# Sheet1.net
KiCad netlist of a schematic drawn in Altium Designer
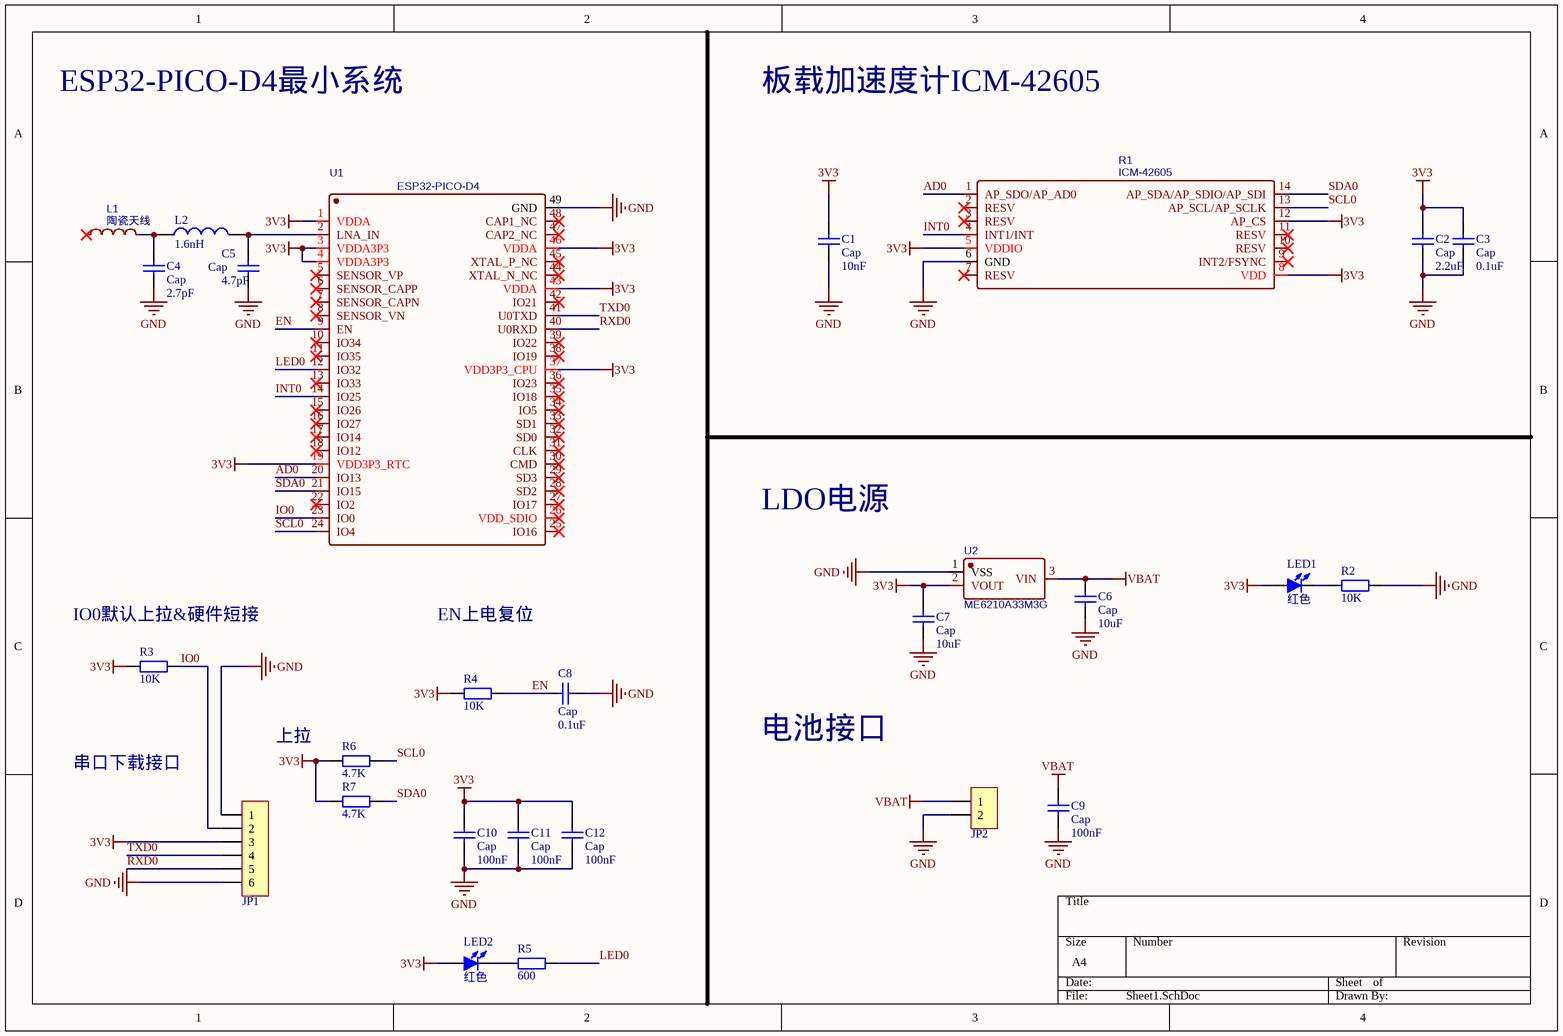
[diagram p0: Sheet1.SchDoc]

(export (version "E")
  (design (tool "Eeschema 10.0.6"))
  (components
    (comp (ref "C1")
      (value "Cap")
      (footprint "C 0402_L")
      (description "Capacitor")
      (fields (field (name "ALTIUM_VALUE") "10nF") (field (name "PUBLISHER") "Altium Limited"))
      (libsource (lib "Miscellaneous Devices") (part "Cap"))
    )
    (comp (ref "C2")
      (value "Cap")
      (footprint "C 0402_L")
      (description "Capacitor")
      (fields (field (name "ALTIUM_VALUE") "2.2uF") (field (name "PUBLISHER") "Altium Limited"))
      (libsource (lib "Miscellaneous Devices") (part "Cap"))
    )
    (comp (ref "C3")
      (value "Cap")
      (footprint "C 0402_L")
      (description "Capacitor")
      (fields (field (name "ALTIUM_VALUE") "0.1uF") (field (name "PUBLISHER") "Altium Limited"))
      (libsource (lib "Miscellaneous Devices") (part "Cap"))
    )
    (comp (ref "C4")
      (value "Cap")
      (footprint "C 0402_L")
      (description "Capacitor")
      (fields (field (name "ALTIUM_VALUE") "2.7pF") (field (name "PUBLISHER") "Altium Limited"))
      (libsource (lib "Miscellaneous Devices") (part "Cap"))
    )
    (comp (ref "C5")
      (value "Cap")
      (footprint "C 0402_L")
      (description "Capacitor")
      (fields (field (name "ALTIUM_VALUE") "4.7pF") (field (name "PUBLISHER") "Altium Limited"))
      (libsource (lib "Miscellaneous Devices") (part "Cap"))
    )
    (comp (ref "C6")
      (value "Cap")
      (footprint "C 0402_L")
      (description "Capacitor")
      (fields (field (name "ALTIUM_VALUE") "10uF") (field (name "PUBLISHER") "Altium Limited"))
      (libsource (lib "Miscellaneous Devices") (part "Cap"))
    )
    (comp (ref "C7")
      (value "Cap")
      (footprint "C 0402_L")
      (description "Capacitor")
      (fields (field (name "ALTIUM_VALUE") "10uF") (field (name "PUBLISHER") "Altium Limited"))
      (libsource (lib "Miscellaneous Devices") (part "Cap"))
    )
    (comp (ref "C8")
      (value "Cap")
      (footprint "C 0402_L")
      (description "Capacitor")
      (fields (field (name "ALTIUM_VALUE") "0.1uF") (field (name "PUBLISHER") "Altium Limited"))
      (libsource (lib "Miscellaneous Devices") (part "Cap"))
    )
    (comp (ref "C9")
      (value "Cap")
      (footprint "C 0402_L")
      (description "Capacitor")
      (fields (field (name "ALTIUM_VALUE") "100nF") (field (name "PUBLISHER") "Altium Limited"))
      (libsource (lib "Miscellaneous Devices") (part "Cap"))
    )
    (comp (ref "C10")
      (value "Cap")
      (footprint "C 0402_L")
      (description "Capacitor")
      (fields (field (name "ALTIUM_VALUE") "100nF") (field (name "PUBLISHER") "Altium Limited"))
      (libsource (lib "Miscellaneous Devices") (part "Cap"))
    )
    (comp (ref "C11")
      (value "Cap")
      (footprint "C 0402_L")
      (description "Capacitor")
      (fields (field (name "ALTIUM_VALUE") "100nF") (field (name "PUBLISHER") "Altium Limited"))
      (libsource (lib "Miscellaneous Devices") (part "Cap"))
    )
    (comp (ref "C12")
      (value "Cap")
      (footprint "C 0402_L")
      (description "Capacitor")
      (fields (field (name "ALTIUM_VALUE") "100nF") (field (name "PUBLISHER") "Altium Limited"))
      (libsource (lib "Miscellaneous Devices") (part "Cap"))
    )
    (comp (ref "JP1")
      (value "HDR-1X6")
      (footprint "debug")
      (description "6P接插件")
      (fields (field (name "版权归属") "源创客"))
      (libsource (lib "Basic_Integrated_Library") (part "Header 6"))
    )
    (comp (ref "JP2")
      (value "HDR-1X2")
      (footprint "电池焊接口")
      (description "2P接插件")
      (fields (field (name "版权归属") "源创客"))
      (libsource (lib "Basic_Integrated_Library") (part "Header 2"))
    )
    (comp (ref "L1")
      (value "陶瓷天线")
      (footprint "Huaxin")
      (fields
        (field (name "BOM_SUPPLIER PART") "C127620")
        (field (name "BOM_MANUFACTURER PART") "RFECA3216060A1T")
        (field (name "CONTRIBUTOR") "LCSC")
      )
      (libsource (lib "altium-import") (part "root_0_Huaxin_"))
    )
    (comp (ref "L2")
      (value "1.6nH")
      (footprint "L 0402")
      (description "小功率贴片电感")
      (fields (field (name "版权归属") "源创客"))
      (libsource (lib "Basic_Integrated_Library") (part "L"))
    )
    (comp (ref "LED1")
      (value "红色")
      (footprint "LED 0805G")
      (description "贴片LED")
      (fields (field (name "版权归属") "源创客"))
      (libsource (lib "Basic_Integrated_Library") (part "LED-SMD"))
    )
    (comp (ref "LED2")
      (value "红色")
      (footprint "LED 0805G")
      (description "贴片LED")
      (fields (field (name "版权归属") "源创客"))
      (libsource (lib "Basic_Integrated_Library") (part "LED-SMD"))
    )
    (comp (ref "R1")
      (value "ICM-42605")
      (footprint "ICM-42605")
      (fields (field (name "BOM_SUPPLIER PART") "C2655099") (field (name "CONTRIBUTOR") "LCSC"))
      (libsource (lib "altium-import") (part "root_0_ICM-42605_"))
    )
    (comp (ref "R2")
      (value "10K")
      (footprint "R 0402_L")
      (description "贴片电阻")
      (fields (field (name "版权归属") "源创客"))
      (libsource (lib "Basic_Integrated_Library") (part "R"))
    )
    (comp (ref "R3")
      (value "10K")
      (footprint "R 0402_L")
      (description "贴片电阻")
      (fields (field (name "版权归属") "源创客"))
      (libsource (lib "Basic_Integrated_Library") (part "R"))
    )
    (comp (ref "R4")
      (value "10K")
      (footprint "R 0402_L")
      (description "贴片电阻")
      (fields (field (name "版权归属") "源创客"))
      (libsource (lib "Basic_Integrated_Library") (part "R"))
    )
    (comp (ref "R5")
      (value "600")
      (footprint "R 0402_L")
      (description "贴片电阻")
      (fields (field (name "版权归属") "源创客"))
      (libsource (lib "Basic_Integrated_Library") (part "R"))
    )
    (comp (ref "R6")
      (value "4.7K")
      (footprint "R 0402_L")
      (description "贴片电阻")
      (fields (field (name "版权归属") "源创客"))
      (libsource (lib "Basic_Integrated_Library") (part "R"))
    )
    (comp (ref "R7")
      (value "4.7K")
      (footprint "R 0402_L")
      (description "贴片电阻")
      (fields (field (name "版权归属") "源创客"))
      (libsource (lib "Basic_Integrated_Library") (part "R"))
    )
    (comp (ref "U1")
      (value "ESP32-PICO-D4")
      (footprint "ESP32-PICO-D4")
      (fields (field (name "BOM_SUPPLIER PART") "C193707") (field (name "CONTRIBUTOR") "LCSC"))
      (libsource (lib "altium-import") (part "root_0_ESP32-PICO-D4_"))
    )
    (comp (ref "U2")
      (value "ME6210A33M3G")
      (footprint "ME6210A33M3G")
      (fields (field (name "BOM_SUPPLIER PART") "C236680") (field (name "CONTRIBUTOR") "LCSC"))
      (libsource (lib "altium-import") (part "root_0_ME6210A33M3G_"))
    )
  )
  (nets
    (net (code "1") (name "/AD0") (class "Default")
      (node (ref "R1") (pin "1") (pinfunction "AP_SDO/AP_AD0_1") (pintype "passive"))
      (node (ref "U1") (pin "20") (pinfunction "IO13_20") (pintype "passive"))
    )
    (net (code "2") (name "/EN") (class "Default")
      (node (ref "C8") (pin "2") (pinfunction "2_2") (pintype "passive"))
      (node (ref "R4") (pin "2") (pinfunction "2_2") (pintype "passive"))
      (node (ref "U1") (pin "9") (pinfunction "EN_9") (pintype "passive"))
    )
    (net (code "3") (name "/INT0") (class "Default")
      (node (ref "R1") (pin "4") (pinfunction "INT1/INT_4") (pintype "passive"))
      (node (ref "U1") (pin "14") (pinfunction "IO25_14") (pintype "passive"))
    )
    (net (code "4") (name "/IO0") (class "Default")
      (node (ref "JP1") (pin "2") (pinfunction "2_2") (pintype "passive"))
      (node (ref "R3") (pin "2") (pinfunction "2_2") (pintype "passive"))
      (node (ref "U1") (pin "23") (pinfunction "IO0_23") (pintype "passive"))
    )
    (net (code "5") (name "/LED0") (class "Default")
      (node (ref "R5") (pin "2") (pinfunction "2_2") (pintype "passive"))
      (node (ref "U1") (pin "12") (pinfunction "IO32_12") (pintype "passive"))
    )
    (net (code "6") (name "/RXD0") (class "Default")
      (node (ref "JP1") (pin "5") (pinfunction "5_5") (pintype "passive"))
      (node (ref "U1") (pin "40") (pinfunction "U0RXD_40") (pintype "passive"))
    )
    (net (code "7") (name "/SCL0") (class "Default")
      (node (ref "R1") (pin "13") (pinfunction "AP_SCL/AP_SCLK_13") (pintype "passive"))
      (node (ref "R6") (pin "2") (pinfunction "2_2") (pintype "passive"))
      (node (ref "U1") (pin "24") (pinfunction "IO4_24") (pintype "passive"))
    )
    (net (code "8") (name "/SDA0") (class "Default")
      (node (ref "R1") (pin "14") (pinfunction "AP_SDA/AP_SDIO/AP_SDI_14") (pintype "passive"))
      (node (ref "R7") (pin "2") (pinfunction "2_2") (pintype "passive"))
      (node (ref "U1") (pin "21") (pinfunction "IO15_21") (pintype "passive"))
    )
    (net (code "9") (name "/TXD0") (class "Default")
      (node (ref "JP1") (pin "4") (pinfunction "4_4") (pintype "passive"))
      (node (ref "U1") (pin "41") (pinfunction "U0TXD_41") (pintype "passive"))
    )
    (net (code "10") (name "3V3") (class "Default")
      (node (ref "C1") (pin "2") (pinfunction "2_2") (pintype "passive"))
      (node (ref "C10") (pin "1") (pinfunction "1_1") (pintype "passive"))
      (node (ref "C11") (pin "1") (pinfunction "1_1") (pintype "passive"))
      (node (ref "C12") (pin "1") (pinfunction "1_1") (pintype "passive"))
      (node (ref "C2") (pin "2") (pinfunction "2_2") (pintype "passive"))
      (node (ref "C3") (pin "2") (pinfunction "2_2") (pintype "passive"))
      (node (ref "C7") (pin "2") (pinfunction "2_2") (pintype "passive"))
      (node (ref "JP1") (pin "3") (pinfunction "3_3") (pintype "passive"))
      (node (ref "LED1") (pin "1") (pinfunction "A_1") (pintype "passive"))
      (node (ref "LED2") (pin "1") (pinfunction "A_1") (pintype "passive"))
      (node (ref "R1") (pin "12") (pinfunction "AP_CS_12") (pintype "passive"))
      (node (ref "R1") (pin "5") (pinfunction "VDDIO_5") (pintype "passive"))
      (node (ref "R1") (pin "8") (pinfunction "VDD_8") (pintype "passive"))
      (node (ref "R3") (pin "1") (pinfunction "1_1") (pintype "passive"))
      (node (ref "R4") (pin "1") (pinfunction "1_1") (pintype "passive"))
      (node (ref "R6") (pin "1") (pinfunction "1_1") (pintype "passive"))
      (node (ref "R7") (pin "1") (pinfunction "1_1") (pintype "passive"))
      (node (ref "U1") (pin "1") (pinfunction "VDDA_1") (pintype "passive"))
      (node (ref "U1") (pin "19") (pinfunction "VDD3P3_RTC_19") (pintype "passive"))
      (node (ref "U1") (pin "3") (pinfunction "VDDA3P3_3") (pintype "passive"))
      (node (ref "U1") (pin "37") (pinfunction "VDD3P3_CPU_37") (pintype "passive"))
      (node (ref "U1") (pin "4") (pinfunction "VDDA3P3_4") (pintype "passive"))
      (node (ref "U1") (pin "43") (pinfunction "VDDA_43") (pintype "passive"))
      (node (ref "U1") (pin "46") (pinfunction "VDDA_46") (pintype "passive"))
      (node (ref "U2") (pin "2") (pinfunction "VOUT_2") (pintype "passive"))
    )
    (net (code "11") (name "GND") (class "Default")
      (node (ref "C1") (pin "1") (pinfunction "1_1") (pintype "passive"))
      (node (ref "C10") (pin "2") (pinfunction "2_2") (pintype "passive"))
      (node (ref "C11") (pin "2") (pinfunction "2_2") (pintype "passive"))
      (node (ref "C12") (pin "2") (pinfunction "2_2") (pintype "passive"))
      (node (ref "C2") (pin "1") (pinfunction "1_1") (pintype "passive"))
      (node (ref "C3") (pin "1") (pinfunction "1_1") (pintype "passive"))
      (node (ref "C4") (pin "2") (pinfunction "2_2") (pintype "passive"))
      (node (ref "C5") (pin "2") (pinfunction "2_2") (pintype "passive"))
      (node (ref "C6") (pin "1") (pinfunction "1_1") (pintype "passive"))
      (node (ref "C7") (pin "1") (pinfunction "1_1") (pintype "passive"))
      (node (ref "C8") (pin "1") (pinfunction "1_1") (pintype "passive"))
      (node (ref "C9") (pin "1") (pinfunction "1_1") (pintype "passive"))
      (node (ref "JP1") (pin "1") (pinfunction "1_1") (pintype "passive"))
      (node (ref "JP1") (pin "6") (pinfunction "6_6") (pintype "passive"))
      (node (ref "JP2") (pin "2") (pinfunction "2_2") (pintype "passive"))
      (node (ref "R1") (pin "6") (pinfunction "GND_6") (pintype "passive"))
      (node (ref "R2") (pin "2") (pinfunction "2_2") (pintype "passive"))
      (node (ref "U1") (pin "49") (pinfunction "GND_49") (pintype "passive"))
      (node (ref "U2") (pin "1") (pinfunction "VSS_1") (pintype "passive"))
    )
    (net (code "12") (name "Net-(C4-Pad1)") (class "Default")
      (node (ref "C4") (pin "1") (pinfunction "1_1") (pintype "passive"))
      (node (ref "L1") (pin "2") (pinfunction "2_2") (pintype "passive"))
      (node (ref "L2") (pin "1") (pinfunction "1_1") (pintype "passive"))
    )
    (net (code "13") (name "Net-(LED1-K)") (class "Default")
      (node (ref "LED1") (pin "2") (pinfunction "K_2") (pintype "passive"))
      (node (ref "R2") (pin "1") (pinfunction "1_1") (pintype "passive"))
    )
    (net (code "14") (name "Net-(LED2-K)") (class "Default")
      (node (ref "LED2") (pin "2") (pinfunction "K_2") (pintype "passive"))
      (node (ref "R5") (pin "1") (pinfunction "1_1") (pintype "passive"))
    )
    (net (code "15") (name "Net-(U1-LNA_IN)") (class "Default")
      (node (ref "C5") (pin "1") (pinfunction "1_1") (pintype "passive"))
      (node (ref "L2") (pin "2") (pinfunction "2_2") (pintype "passive"))
      (node (ref "U1") (pin "2") (pinfunction "LNA_IN_2") (pintype "passive"))
    )
    (net (code "16") (name "VBAT") (class "Default")
      (node (ref "C6") (pin "2") (pinfunction "2_2") (pintype "passive"))
      (node (ref "C9") (pin "2") (pinfunction "2_2") (pintype "passive"))
      (node (ref "JP2") (pin "1") (pinfunction "1_1") (pintype "passive"))
      (node (ref "U2") (pin "3") (pinfunction "VIN_3") (pintype "passive"))
    )
    (net (code "17") (name "unconnected-(L1-Pad1)") (class "Default")
      (node (ref "L1") (pin "1") (pinfunction "1_1") (pintype "passive+no_connect"))
    )
    (net (code "18") (name "unconnected-(R1-INT2{slash}FSYNC-Pad9)") (class "Default")
      (node (ref "R1") (pin "9") (pinfunction "INT2/FSYNC_9") (pintype "passive+no_connect"))
    )
    (net (code "19") (name "unconnected-(R1-RESV-Pad2)") (class "Default")
      (node (ref "R1") (pin "2") (pinfunction "RESV_2") (pintype "passive+no_connect"))
    )
    (net (code "20") (name "unconnected-(R1-RESV-Pad3)") (class "Default")
      (node (ref "R1") (pin "3") (pinfunction "RESV_3") (pintype "passive+no_connect"))
    )
    (net (code "21") (name "unconnected-(R1-RESV-Pad7)") (class "Default")
      (node (ref "R1") (pin "7") (pinfunction "RESV_7") (pintype "passive+no_connect"))
    )
    (net (code "22") (name "unconnected-(R1-RESV-Pad10)") (class "Default")
      (node (ref "R1") (pin "10") (pinfunction "RESV_10") (pintype "passive+no_connect"))
    )
    (net (code "23") (name "unconnected-(R1-RESV-Pad11)") (class "Default")
      (node (ref "R1") (pin "11") (pinfunction "RESV_11") (pintype "passive+no_connect"))
    )
    (net (code "24") (name "unconnected-(U1-CAP1_NC-Pad48)") (class "Default")
      (node (ref "U1") (pin "48") (pinfunction "CAP1_NC_48") (pintype "passive+no_connect"))
    )
    (net (code "25") (name "unconnected-(U1-CAP2_NC-Pad47)") (class "Default")
      (node (ref "U1") (pin "47") (pinfunction "CAP2_NC_47") (pintype "passive+no_connect"))
    )
    (net (code "26") (name "unconnected-(U1-CLK-Pad31)") (class "Default")
      (node (ref "U1") (pin "31") (pinfunction "CLK_31") (pintype "passive+no_connect"))
    )
    (net (code "27") (name "unconnected-(U1-CMD-Pad30)") (class "Default")
      (node (ref "U1") (pin "30") (pinfunction "CMD_30") (pintype "passive+no_connect"))
    )
    (net (code "28") (name "unconnected-(U1-IO2-Pad22)") (class "Default")
      (node (ref "U1") (pin "22") (pinfunction "IO2_22") (pintype "passive+no_connect"))
    )
    (net (code "29") (name "unconnected-(U1-IO5-Pad34)") (class "Default")
      (node (ref "U1") (pin "34") (pinfunction "IO5_34") (pintype "passive+no_connect"))
    )
    (net (code "30") (name "unconnected-(U1-IO12-Pad18)") (class "Default")
      (node (ref "U1") (pin "18") (pinfunction "IO12_18") (pintype "passive+no_connect"))
    )
    (net (code "31") (name "unconnected-(U1-IO14-Pad17)") (class "Default")
      (node (ref "U1") (pin "17") (pinfunction "IO14_17") (pintype "passive+no_connect"))
    )
    (net (code "32") (name "unconnected-(U1-IO16-Pad25)") (class "Default")
      (node (ref "U1") (pin "25") (pinfunction "IO16_25") (pintype "passive+no_connect"))
    )
    (net (code "33") (name "unconnected-(U1-IO17-Pad27)") (class "Default")
      (node (ref "U1") (pin "27") (pinfunction "IO17_27") (pintype "passive+no_connect"))
    )
    (net (code "34") (name "unconnected-(U1-IO18-Pad35)") (class "Default")
      (node (ref "U1") (pin "35") (pinfunction "IO18_35") (pintype "passive+no_connect"))
    )
    (net (code "35") (name "unconnected-(U1-IO19-Pad38)") (class "Default")
      (node (ref "U1") (pin "38") (pinfunction "IO19_38") (pintype "passive+no_connect"))
    )
    (net (code "36") (name "unconnected-(U1-IO21-Pad42)") (class "Default")
      (node (ref "U1") (pin "42") (pinfunction "IO21_42") (pintype "passive+no_connect"))
    )
    (net (code "37") (name "unconnected-(U1-IO22-Pad39)") (class "Default")
      (node (ref "U1") (pin "39") (pinfunction "IO22_39") (pintype "passive+no_connect"))
    )
    (net (code "38") (name "unconnected-(U1-IO23-Pad36)") (class "Default")
      (node (ref "U1") (pin "36") (pinfunction "IO23_36") (pintype "passive+no_connect"))
    )
    (net (code "39") (name "unconnected-(U1-IO26-Pad15)") (class "Default")
      (node (ref "U1") (pin "15") (pinfunction "IO26_15") (pintype "passive+no_connect"))
    )
    (net (code "40") (name "unconnected-(U1-IO27-Pad16)") (class "Default")
      (node (ref "U1") (pin "16") (pinfunction "IO27_16") (pintype "passive+no_connect"))
    )
    (net (code "41") (name "unconnected-(U1-IO33-Pad13)") (class "Default")
      (node (ref "U1") (pin "13") (pinfunction "IO33_13") (pintype "passive+no_connect"))
    )
    (net (code "42") (name "unconnected-(U1-IO34-Pad10)") (class "Default")
      (node (ref "U1") (pin "10") (pinfunction "IO34_10") (pintype "passive+no_connect"))
    )
    (net (code "43") (name "unconnected-(U1-IO35-Pad11)") (class "Default")
      (node (ref "U1") (pin "11") (pinfunction "IO35_11") (pintype "passive+no_connect"))
    )
    (net (code "44") (name "unconnected-(U1-SD0-Pad32)") (class "Default")
      (node (ref "U1") (pin "32") (pinfunction "SD0_32") (pintype "passive+no_connect"))
    )
    (net (code "45") (name "unconnected-(U1-SD1-Pad33)") (class "Default")
      (node (ref "U1") (pin "33") (pinfunction "SD1_33") (pintype "passive+no_connect"))
    )
    (net (code "46") (name "unconnected-(U1-SD2-Pad28)") (class "Default")
      (node (ref "U1") (pin "28") (pinfunction "SD2_28") (pintype "passive+no_connect"))
    )
    (net (code "47") (name "unconnected-(U1-SD3-Pad29)") (class "Default")
      (node (ref "U1") (pin "29") (pinfunction "SD3_29") (pintype "passive+no_connect"))
    )
    (net (code "48") (name "unconnected-(U1-SENSOR_CAPN-Pad7)") (class "Default")
      (node (ref "U1") (pin "7") (pinfunction "SENSOR_CAPN_7") (pintype "passive+no_connect"))
    )
    (net (code "49") (name "unconnected-(U1-SENSOR_CAPP-Pad6)") (class "Default")
      (node (ref "U1") (pin "6") (pinfunction "SENSOR_CAPP_6") (pintype "passive+no_connect"))
    )
    (net (code "50") (name "unconnected-(U1-SENSOR_VN-Pad8)") (class "Default")
      (node (ref "U1") (pin "8") (pinfunction "SENSOR_VN_8") (pintype "passive+no_connect"))
    )
    (net (code "51") (name "unconnected-(U1-SENSOR_VP-Pad5)") (class "Default")
      (node (ref "U1") (pin "5") (pinfunction "SENSOR_VP_5") (pintype "passive+no_connect"))
    )
    (net (code "52") (name "unconnected-(U1-VDD_SDIO-Pad26)") (class "Default")
      (node (ref "U1") (pin "26") (pinfunction "VDD_SDIO_26") (pintype "passive+no_connect"))
    )
    (net (code "53") (name "unconnected-(U1-XTAL_N_NC-Pad44)") (class "Default")
      (node (ref "U1") (pin "44") (pinfunction "XTAL_N_NC_44") (pintype "passive+no_connect"))
    )
    (net (code "54") (name "unconnected-(U1-XTAL_P_NC-Pad45)") (class "Default")
      (node (ref "U1") (pin "45") (pinfunction "XTAL_P_NC_45") (pintype "passive+no_connect"))
    )
  )
)
